# Connectors.net
KiCad netlist of a schematic drawn in Altium Designer
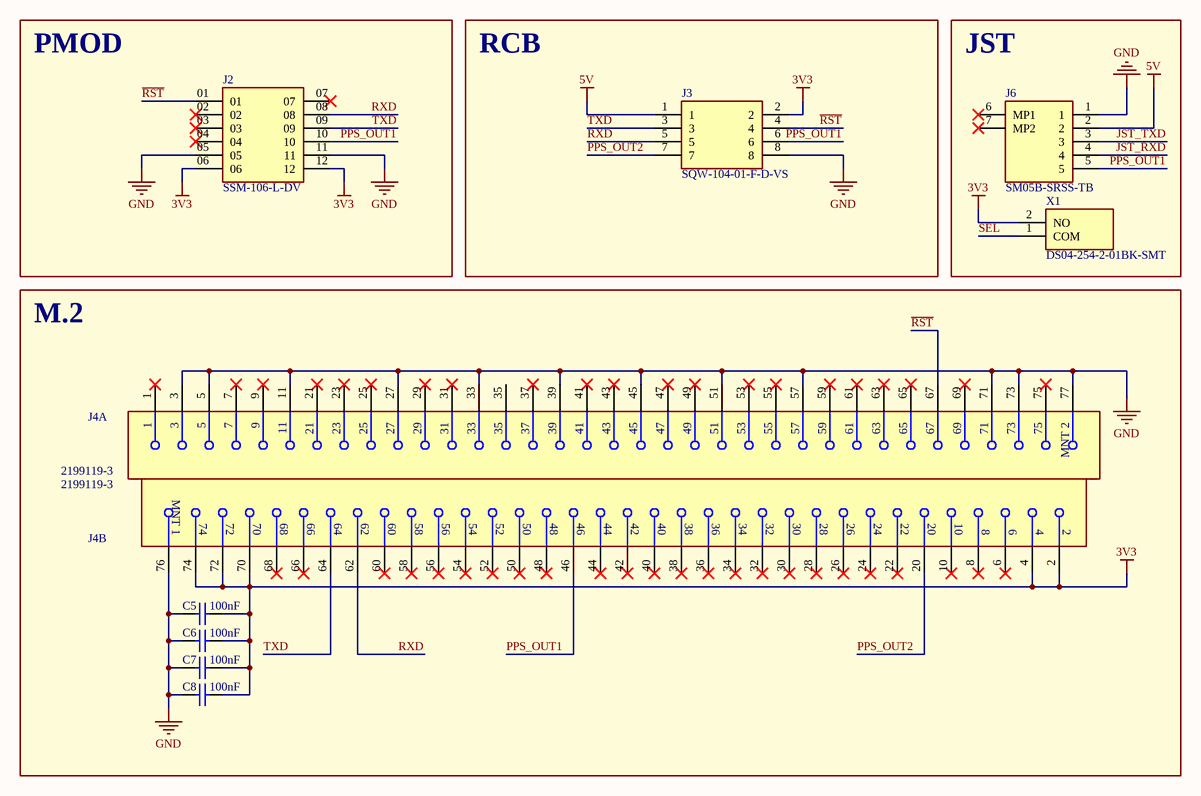
[diagram p0: Connectors.SchDoc]

(export (version "E")
  (design (tool "Eeschema 10.0.6"))
  (components
    (comp (ref "C5")
      (value "100nF")
      (footprint "FP-C0603C-CF-MFG")
      (description "Cap Ceramic 0.1uF 16V X7R 10% SMD 0603 125°C Paper T/R")
      (fields (field (name "VOLTAGE") "16V") (field (name "TOLERANCE") "10%"))
      (libsource (lib "NetTimeLogic GmbH") (part "C0402C104K8PACTU"))
    )
    (comp (ref "C6")
      (value "100nF")
      (footprint "FP-C0603C-CF-MFG")
      (description "Cap Ceramic 0.1uF 16V X7R 10% SMD 0603 125°C Paper T/R")
      (fields (field (name "VOLTAGE") "16V") (field (name "TOLERANCE") "10%"))
      (libsource (lib "NetTimeLogic GmbH") (part "C0402C104K8PACTU"))
    )
    (comp (ref "C7")
      (value "100nF")
      (footprint "FP-C0603C-CF-MFG")
      (description "Cap Ceramic 0.1uF 16V X7R 10% SMD 0603 125°C Paper T/R")
      (fields (field (name "VOLTAGE") "16V") (field (name "TOLERANCE") "10%"))
      (libsource (lib "NetTimeLogic GmbH") (part "C0402C104K8PACTU"))
    )
    (comp (ref "C8")
      (value "100nF")
      (footprint "FP-C0603C-CF-MFG")
      (description "Cap Ceramic 0.1uF 16V X7R 10% SMD 0603 125°C Paper T/R")
      (fields (field (name "VOLTAGE") "16V") (field (name "TOLERANCE") "10%"))
      (libsource (lib "NetTimeLogic GmbH") (part "C0402C104K8PACTU"))
    )
    (comp (ref "J2")
      (value "SSM-106-L-DV")
      (footprint "SAMTEC_SSM-106-L-DV")
      (description "Header Surface Mount (2.54mm) 2x6")
      (fields (field (name "MF") "Samtec"))
      (libsource (lib "NetTimeLogic GmbH") (part "SSM-106-L-DV"))
    )
    (comp (ref "J3")
      (value "SQW-104-01-F-D-VS")
      (footprint "SAMTEC-SQW-104-01-X-D-VS")
      (description "Headers & Wire Housings Cost Effective Rugged PCB Sockets, 2.00mm pitch")
      (fields (field (name "MP") "SAMTEC-SQW-104-01-X-D-VS"))
      (libsource (lib "NetTimeLogic GmbH") (part "SQW-104-01-F-D-VS"))
    )
    (comp (ref "J4")
      (value "2199119-3")
      (footprint "FP-2199119-3-MFG")
      (description "Conn Card Edge SKT 67 POS 0.5mm Solder RA SMD Embossed T/R")
      (libsource (lib "NetTimeLogic GmbH") (part "a14843ccfa78e5d0b739856168502fb"))
    )
    (comp (ref "J6")
      (value "SM05B-SRSS-TB")
      (footprint "SM05BSRSSTBLFSN")
      (description "Board Connector, 5 Contact(s), 1 Row(s), Male, Right Angle, Surface Mount Terminal")
      (fields (field (name "MANUFACTURER_PART_NUMBER") "SM05B-SRSS-TB(LF)(SN)"))
      (libsource (lib "NetTimeLogic GmbH") (part "SM05B-SRSS-TB_LF__SN_"))
    )
    (comp (ref "X1")
      (value "DS04-254-2-01BK-SMT")
      (footprint "DS04254201BKSMTTR")
      (description "Switch DIP OFF ON SPST 1 Flat Slide 0.025A 24VDC Gull Wing 2.54mm SMD Tube")
      (fields
        (field (name "MOUSER PART NUMBER") "490-DS04254201BK-STR")
        (field (name "MANUFACTURER_PART_NUMBER") "DS04-254-2-01BK-SMT-TR")
      )
      (libsource (lib "NetTimeLogic GmbH") (part "DS04-254-2-01BK-SMT-TR"))
    )
  )
  (nets
    (net (code "1") (name "/JST_RXD") (class "Default")
      (node (ref "J6") (pin "4") (pinfunction "4_4") (pintype "passive"))
    )
    (net (code "2") (name "/JST_TXD") (class "Default")
      (node (ref "J6") (pin "3") (pinfunction "3_3") (pintype "passive"))
    )
    (net (code "3") (name "/PPS_OUT1") (class "Default")
      (node (ref "J2") (pin "10") (pinfunction "10_10") (pintype "passive"))
      (node (ref "J3") (pin "6") (pinfunction "6_6") (pintype "passive"))
      (node (ref "J4") (pin "46") (pinfunction "46_46") (pintype "passive"))
      (node (ref "J6") (pin "5") (pinfunction "5_5") (pintype "passive"))
    )
    (net (code "4") (name "/PPS_OUT2") (class "Default")
      (node (ref "J3") (pin "7") (pinfunction "7_7") (pintype "passive"))
      (node (ref "J4") (pin "20") (pinfunction "20_20") (pintype "passive"))
    )
    (net (code "5") (name "/RXD") (class "Default")
      (node (ref "J2") (pin "08") (pinfunction "08_08") (pintype "passive"))
      (node (ref "J3") (pin "5") (pinfunction "5_5") (pintype "passive"))
      (node (ref "J4") (pin "62") (pinfunction "62_62") (pintype "passive"))
    )
    (net (code "6") (name "/SEL") (class "Default")
      (node (ref "X1") (pin "1") (pinfunction "COM_1") (pintype "passive"))
    )
    (net (code "7") (name "/TXD") (class "Default")
      (node (ref "J2") (pin "09") (pinfunction "09_09") (pintype "passive"))
      (node (ref "J3") (pin "3") (pinfunction "3_3") (pintype "passive"))
      (node (ref "J4") (pin "64") (pinfunction "64_64") (pintype "passive"))
    )
    (net (code "8") (name "/~{RST}") (class "Default")
      (node (ref "J2") (pin "01") (pinfunction "01_01") (pintype "passive"))
      (node (ref "J3") (pin "4") (pinfunction "4_4") (pintype "passive"))
      (node (ref "J4") (pin "67") (pinfunction "67_67") (pintype "passive"))
    )
    (net (code "9") (name "3V3") (class "Default")
      (node (ref "C5") (pin "2") (pinfunction "2_2") (pintype "passive"))
      (node (ref "C6") (pin "2") (pinfunction "2_2") (pintype "passive"))
      (node (ref "C7") (pin "2") (pinfunction "2_2") (pintype "passive"))
      (node (ref "C8") (pin "2") (pinfunction "2_2") (pintype "passive"))
      (node (ref "J2") (pin "06") (pinfunction "06_06") (pintype "passive"))
      (node (ref "J2") (pin "12") (pinfunction "12_12") (pintype "passive"))
      (node (ref "J3") (pin "2") (pinfunction "2_2") (pintype "passive"))
      (node (ref "J4") (pin "2") (pinfunction "2_2") (pintype "passive"))
      (node (ref "J4") (pin "4") (pinfunction "4_4") (pintype "passive"))
      (node (ref "J4") (pin "70") (pinfunction "70_70") (pintype "passive"))
      (node (ref "J4") (pin "72") (pinfunction "72_72") (pintype "passive"))
      (node (ref "J4") (pin "74") (pinfunction "74_74") (pintype "passive"))
      (node (ref "X1") (pin "2") (pinfunction "NO_2") (pintype "passive"))
    )
    (net (code "10") (name "5V") (class "Default")
      (node (ref "J3") (pin "1") (pinfunction "1_1") (pintype "passive"))
      (node (ref "J6") (pin "2") (pinfunction "2_2") (pintype "passive"))
    )
    (net (code "11") (name "GND") (class "Default")
      (node (ref "C5") (pin "1") (pinfunction "1_1") (pintype "passive"))
      (node (ref "C6") (pin "1") (pinfunction "1_1") (pintype "passive"))
      (node (ref "C7") (pin "1") (pinfunction "1_1") (pintype "passive"))
      (node (ref "C8") (pin "1") (pinfunction "1_1") (pintype "passive"))
      (node (ref "J2") (pin "05") (pinfunction "05_05") (pintype "passive"))
      (node (ref "J2") (pin "11") (pinfunction "11_11") (pintype "passive"))
      (node (ref "J3") (pin "8") (pinfunction "8_8") (pintype "passive"))
      (node (ref "J4") (pin "11") (pinfunction "11_11") (pintype "passive"))
      (node (ref "J4") (pin "27") (pinfunction "27_27") (pintype "passive"))
      (node (ref "J4") (pin "3") (pinfunction "3_3") (pintype "passive"))
      (node (ref "J4") (pin "33") (pinfunction "33_33") (pintype "passive"))
      (node (ref "J4") (pin "39") (pinfunction "39_39") (pintype "passive"))
      (node (ref "J4") (pin "45") (pinfunction "45_45") (pintype "passive"))
      (node (ref "J4") (pin "5") (pinfunction "5_5") (pintype "passive"))
      (node (ref "J4") (pin "51") (pinfunction "51_51") (pintype "passive"))
      (node (ref "J4") (pin "57") (pinfunction "57_57") (pintype "passive"))
      (node (ref "J4") (pin "71") (pinfunction "71_71") (pintype "passive"))
      (node (ref "J4") (pin "73") (pinfunction "73_73") (pintype "passive"))
      (node (ref "J4") (pin "76") (pinfunction "MNT_1_76") (pintype "passive"))
      (node (ref "J4") (pin "77") (pinfunction "MNT_2_77") (pintype "passive"))
      (node (ref "J6") (pin "1") (pinfunction "1_1") (pintype "passive"))
    )
    (net (code "12") (name "unconnected-(J2-Pad02)") (class "Default")
      (node (ref "J2") (pin "02") (pinfunction "02_02") (pintype "passive+no_connect"))
    )
    (net (code "13") (name "unconnected-(J2-Pad03)") (class "Default")
      (node (ref "J2") (pin "03") (pinfunction "03_03") (pintype "passive+no_connect"))
    )
    (net (code "14") (name "unconnected-(J2-Pad04)") (class "Default")
      (node (ref "J2") (pin "04") (pinfunction "04_04") (pintype "passive+no_connect"))
    )
    (net (code "15") (name "unconnected-(J2-Pad07)") (class "Default")
      (node (ref "J2") (pin "07") (pinfunction "07_07") (pintype "passive+no_connect"))
    )
    (net (code "16") (name "unconnected-(J4-Pad1)") (class "Default")
      (node (ref "J4") (pin "1") (pinfunction "1_1") (pintype "passive+no_connect"))
    )
    (net (code "17") (name "unconnected-(J4-Pad6)") (class "Default")
      (node (ref "J4") (pin "6") (pinfunction "6_6") (pintype "passive+no_connect"))
    )
    (net (code "18") (name "unconnected-(J4-Pad7)") (class "Default")
      (node (ref "J4") (pin "7") (pinfunction "7_7") (pintype "passive+no_connect"))
    )
    (net (code "19") (name "unconnected-(J4-Pad8)") (class "Default")
      (node (ref "J4") (pin "8") (pinfunction "8_8") (pintype "passive+no_connect"))
    )
    (net (code "20") (name "unconnected-(J4-Pad9)") (class "Default")
      (node (ref "J4") (pin "9") (pinfunction "9_9") (pintype "passive+no_connect"))
    )
    (net (code "21") (name "unconnected-(J4-Pad10)") (class "Default")
      (node (ref "J4") (pin "10") (pinfunction "10_10") (pintype "passive+no_connect"))
    )
    (net (code "22") (name "unconnected-(J4-Pad21)") (class "Default")
      (node (ref "J4") (pin "21") (pinfunction "21_21") (pintype "passive+no_connect"))
    )
    (net (code "23") (name "unconnected-(J4-Pad22)") (class "Default")
      (node (ref "J4") (pin "22") (pinfunction "22_22") (pintype "passive+no_connect"))
    )
    (net (code "24") (name "unconnected-(J4-Pad23)") (class "Default")
      (node (ref "J4") (pin "23") (pinfunction "23_23") (pintype "passive+no_connect"))
    )
    (net (code "25") (name "unconnected-(J4-Pad24)") (class "Default")
      (node (ref "J4") (pin "24") (pinfunction "24_24") (pintype "passive+no_connect"))
    )
    (net (code "26") (name "unconnected-(J4-Pad25)") (class "Default")
      (node (ref "J4") (pin "25") (pinfunction "25_25") (pintype "passive+no_connect"))
    )
    (net (code "27") (name "unconnected-(J4-Pad26)") (class "Default")
      (node (ref "J4") (pin "26") (pinfunction "26_26") (pintype "passive+no_connect"))
    )
    (net (code "28") (name "unconnected-(J4-Pad28)") (class "Default")
      (node (ref "J4") (pin "28") (pinfunction "28_28") (pintype "passive+no_connect"))
    )
    (net (code "29") (name "unconnected-(J4-Pad29)") (class "Default")
      (node (ref "J4") (pin "29") (pinfunction "29_29") (pintype "passive+no_connect"))
    )
    (net (code "30") (name "unconnected-(J4-Pad30)") (class "Default")
      (node (ref "J4") (pin "30") (pinfunction "30_30") (pintype "passive+no_connect"))
    )
    (net (code "31") (name "unconnected-(J4-Pad31)") (class "Default")
      (node (ref "J4") (pin "31") (pinfunction "31_31") (pintype "passive+no_connect"))
    )
    (net (code "32") (name "unconnected-(J4-Pad32)") (class "Default")
      (node (ref "J4") (pin "32") (pinfunction "32_32") (pintype "passive+no_connect"))
    )
    (net (code "33") (name "unconnected-(J4-Pad34)") (class "Default")
      (node (ref "J4") (pin "34") (pinfunction "34_34") (pintype "passive+no_connect"))
    )
    (net (code "34") (name "unconnected-(J4-Pad35)") (class "Default")
      (node (ref "J4") (pin "35") (pinfunction "35_35") (pintype "passive"))
    )
    (net (code "35") (name "unconnected-(J4-Pad36)") (class "Default")
      (node (ref "J4") (pin "36") (pinfunction "36_36") (pintype "passive+no_connect"))
    )
    (net (code "36") (name "unconnected-(J4-Pad37)") (class "Default")
      (node (ref "J4") (pin "37") (pinfunction "37_37") (pintype "passive+no_connect"))
    )
    (net (code "37") (name "unconnected-(J4-Pad38)") (class "Default")
      (node (ref "J4") (pin "38") (pinfunction "38_38") (pintype "passive+no_connect"))
    )
    (net (code "38") (name "unconnected-(J4-Pad40)") (class "Default")
      (node (ref "J4") (pin "40") (pinfunction "40_40") (pintype "passive+no_connect"))
    )
    (net (code "39") (name "unconnected-(J4-Pad41)") (class "Default")
      (node (ref "J4") (pin "41") (pinfunction "41_41") (pintype "passive+no_connect"))
    )
    (net (code "40") (name "unconnected-(J4-Pad42)") (class "Default")
      (node (ref "J4") (pin "42") (pinfunction "42_42") (pintype "passive+no_connect"))
    )
    (net (code "41") (name "unconnected-(J4-Pad43)") (class "Default")
      (node (ref "J4") (pin "43") (pinfunction "43_43") (pintype "passive+no_connect"))
    )
    (net (code "42") (name "unconnected-(J4-Pad44)") (class "Default")
      (node (ref "J4") (pin "44") (pinfunction "44_44") (pintype "passive+no_connect"))
    )
    (net (code "43") (name "unconnected-(J4-Pad47)") (class "Default")
      (node (ref "J4") (pin "47") (pinfunction "47_47") (pintype "passive+no_connect"))
    )
    (net (code "44") (name "unconnected-(J4-Pad48)") (class "Default")
      (node (ref "J4") (pin "48") (pinfunction "48_48") (pintype "passive+no_connect"))
    )
    (net (code "45") (name "unconnected-(J4-Pad49)") (class "Default")
      (node (ref "J4") (pin "49") (pinfunction "49_49") (pintype "passive+no_connect"))
    )
    (net (code "46") (name "unconnected-(J4-Pad50)") (class "Default")
      (node (ref "J4") (pin "50") (pinfunction "50_50") (pintype "passive+no_connect"))
    )
    (net (code "47") (name "unconnected-(J4-Pad52)") (class "Default")
      (node (ref "J4") (pin "52") (pinfunction "52_52") (pintype "passive+no_connect"))
    )
    (net (code "48") (name "unconnected-(J4-Pad53)") (class "Default")
      (node (ref "J4") (pin "53") (pinfunction "53_53") (pintype "passive+no_connect"))
    )
    (net (code "49") (name "unconnected-(J4-Pad54)") (class "Default")
      (node (ref "J4") (pin "54") (pinfunction "54_54") (pintype "passive+no_connect"))
    )
    (net (code "50") (name "unconnected-(J4-Pad55)") (class "Default")
      (node (ref "J4") (pin "55") (pinfunction "55_55") (pintype "passive+no_connect"))
    )
    (net (code "51") (name "unconnected-(J4-Pad56)") (class "Default")
      (node (ref "J4") (pin "56") (pinfunction "56_56") (pintype "passive+no_connect"))
    )
    (net (code "52") (name "unconnected-(J4-Pad58)") (class "Default")
      (node (ref "J4") (pin "58") (pinfunction "58_58") (pintype "passive+no_connect"))
    )
    (net (code "53") (name "unconnected-(J4-Pad59)") (class "Default")
      (node (ref "J4") (pin "59") (pinfunction "59_59") (pintype "passive+no_connect"))
    )
    (net (code "54") (name "unconnected-(J4-Pad60)") (class "Default")
      (node (ref "J4") (pin "60") (pinfunction "60_60") (pintype "passive+no_connect"))
    )
    (net (code "55") (name "unconnected-(J4-Pad61)") (class "Default")
      (node (ref "J4") (pin "61") (pinfunction "61_61") (pintype "passive+no_connect"))
    )
    (net (code "56") (name "unconnected-(J4-Pad63)") (class "Default")
      (node (ref "J4") (pin "63") (pinfunction "63_63") (pintype "passive+no_connect"))
    )
    (net (code "57") (name "unconnected-(J4-Pad65)") (class "Default")
      (node (ref "J4") (pin "65") (pinfunction "65_65") (pintype "passive+no_connect"))
    )
    (net (code "58") (name "unconnected-(J4-Pad66)") (class "Default")
      (node (ref "J4") (pin "66") (pinfunction "66_66") (pintype "passive+no_connect"))
    )
    (net (code "59") (name "unconnected-(J4-Pad68)") (class "Default")
      (node (ref "J4") (pin "68") (pinfunction "68_68") (pintype "passive+no_connect"))
    )
    (net (code "60") (name "unconnected-(J4-Pad69)") (class "Default")
      (node (ref "J4") (pin "69") (pinfunction "69_69") (pintype "passive+no_connect"))
    )
    (net (code "61") (name "unconnected-(J4-Pad75)") (class "Default")
      (node (ref "J4") (pin "75") (pinfunction "75_75") (pintype "passive+no_connect"))
    )
    (net (code "62") (name "unconnected-(J6-MP1-Pad6)") (class "Default")
      (node (ref "J6") (pin "6") (pinfunction "MP1_6") (pintype "passive+no_connect"))
    )
    (net (code "63") (name "unconnected-(J6-MP2-Pad7)") (class "Default")
      (node (ref "J6") (pin "7") (pinfunction "MP2_7") (pintype "passive+no_connect"))
    )
  )
)
